# arm_controller_single_v1_1.net
KiCad netlist of a schematic drawn in EAGLE
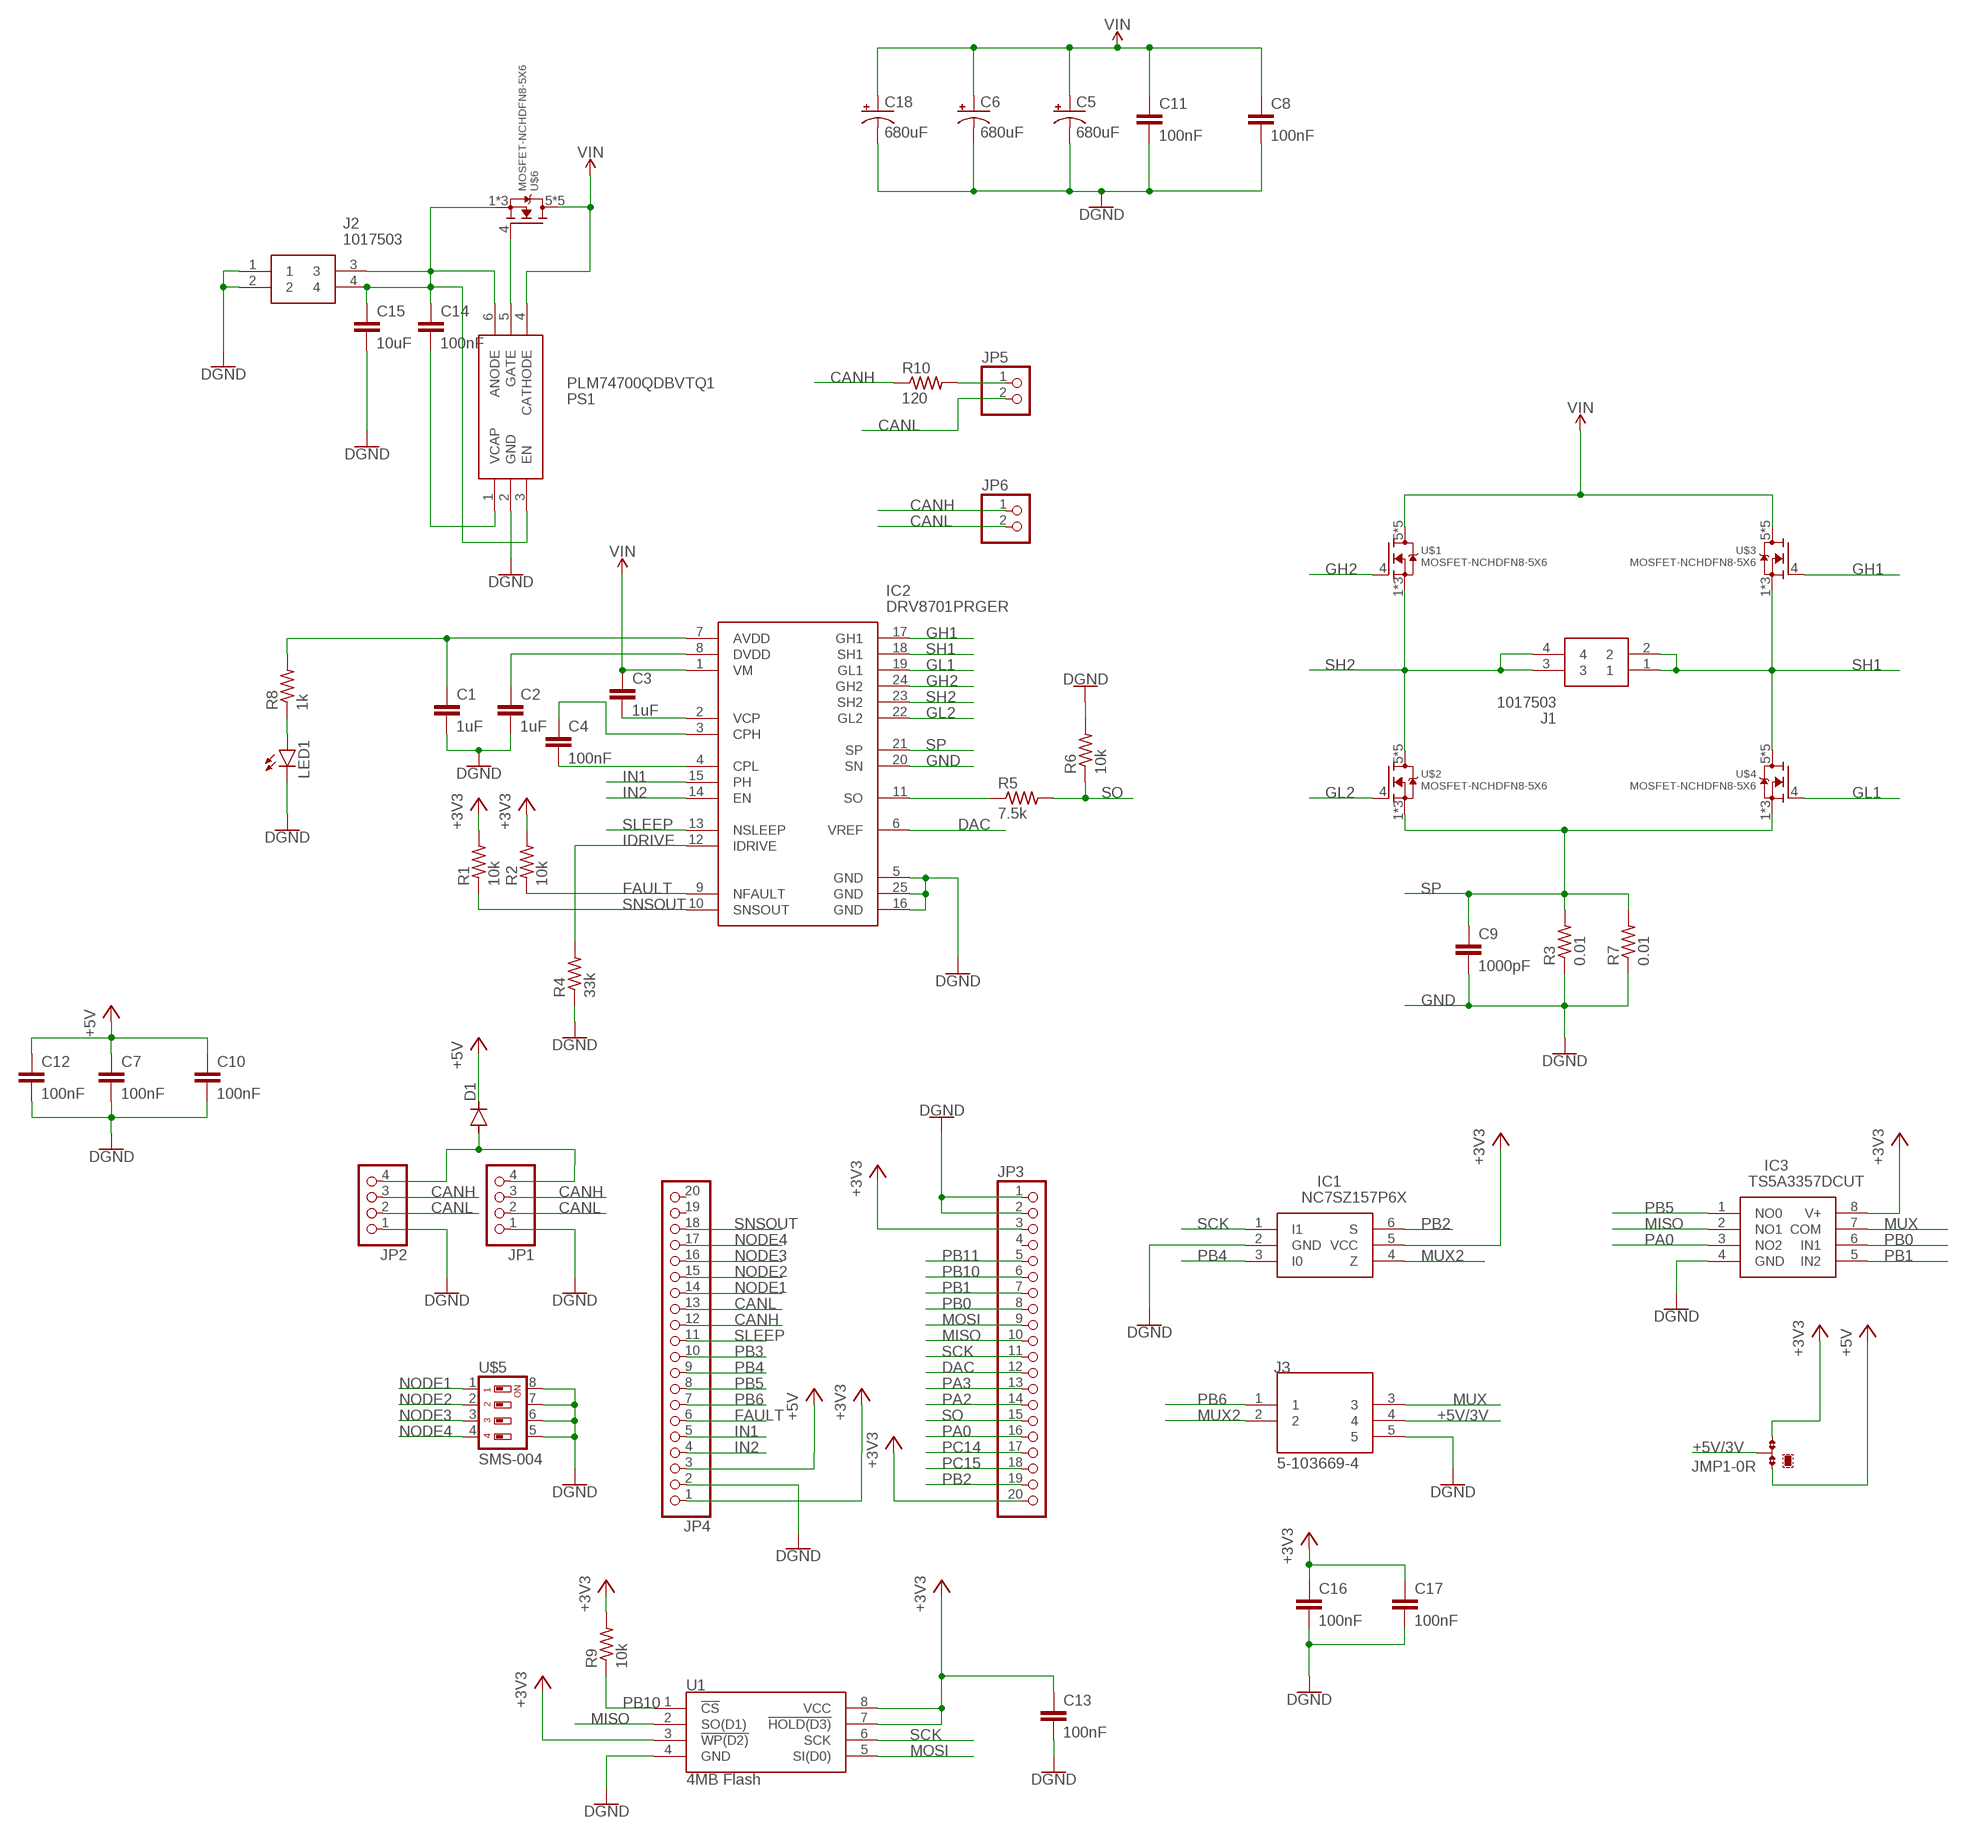
[diagram p0: schematic, sheet 1]

(export (version "E")
  (design (tool "Eeschema 10.0.6"))
  (components
    (comp (ref "C1")
      (value "1uF")
      (footprint "eagle-import:C0603")
      (libsource (lib "eagle-import") (part "C-EUC0603"))
    )
    (comp (ref "C2")
      (value "1uF")
      (footprint "eagle-import:C0603")
      (libsource (lib "eagle-import") (part "C-EUC0603"))
    )
    (comp (ref "C3")
      (value "1uF")
      (footprint "eagle-import:C0603")
      (libsource (lib "eagle-import") (part "C-EUC0603"))
    )
    (comp (ref "C4")
      (value "100nF")
      (footprint "eagle-import:C0603")
      (libsource (lib "eagle-import") (part "C-EUC0603"))
    )
    (comp (ref "C5")
      (value "680uF")
      (footprint "eagle-import:E5-10,5")
      (libsource (lib "eagle-import") (part "CPOL-USE5-10.5"))
    )
    (comp (ref "C6")
      (value "680uF")
      (footprint "eagle-import:E5-10,5")
      (libsource (lib "eagle-import") (part "CPOL-USE5-10.5"))
    )
    (comp (ref "C7")
      (value "100nF")
      (footprint "eagle-import:C0603")
      (libsource (lib "eagle-import") (part "C-EUC0603"))
    )
    (comp (ref "C8")
      (value "100nF")
      (footprint "eagle-import:C0603")
      (libsource (lib "eagle-import") (part "C-EUC0603"))
    )
    (comp (ref "C9")
      (value "1000pF")
      (footprint "eagle-import:C0603")
      (libsource (lib "eagle-import") (part "C-EUC0603"))
    )
    (comp (ref "C10")
      (value "100nF")
      (footprint "eagle-import:C0603")
      (libsource (lib "eagle-import") (part "C-EUC0603"))
    )
    (comp (ref "C11")
      (value "100nF")
      (footprint "eagle-import:C0603")
      (libsource (lib "eagle-import") (part "C-EUC0603"))
    )
    (comp (ref "C12")
      (value "100nF")
      (footprint "eagle-import:C0603")
      (libsource (lib "eagle-import") (part "C-EUC0603"))
    )
    (comp (ref "C13")
      (value "100nF")
      (footprint "eagle-import:C0603")
      (libsource (lib "eagle-import") (part "C-EUC0603"))
    )
    (comp (ref "C14")
      (value "100nF")
      (footprint "eagle-import:C0603")
      (libsource (lib "eagle-import") (part "C-EUC0603"))
    )
    (comp (ref "C15")
      (value "10uF")
      (footprint "eagle-import:C1206")
      (libsource (lib "eagle-import") (part "C-EUC1206"))
    )
    (comp (ref "C16")
      (value "100nF")
      (footprint "eagle-import:C0603")
      (libsource (lib "eagle-import") (part "C-EUC0603"))
    )
    (comp (ref "C17")
      (value "100nF")
      (footprint "eagle-import:C0603")
      (libsource (lib "eagle-import") (part "C-EUC0603"))
    )
    (comp (ref "C18")
      (value "680uF")
      (footprint "eagle-import:E5-10,5")
      (libsource (lib "eagle-import") (part "CPOL-USE5-10.5"))
    )
    (comp (ref "D1")
      (value "CGRM4001-G")
      (footprint "eagle-import:SOD-123_MINI-SMA")
      (libsource (lib "eagle-import") (part "CGRM400-G1"))
    )
    (comp (ref "IC1")
      (value "NC7SZ157P6X")
      (footprint "eagle-import:SOT65P210X110-6N")
      (fields (field (name "MOUSER_PART_NUMBER") "512-NC7SZ157P6X"))
      (libsource (lib "eagle-import") (part "NC7SZ157P6X"))
    )
    (comp (ref "IC2")
      (value "DRV8701PRGER")
      (footprint "eagle-import:QFN50P400X400X100-25N")
      (fields (field (name "MOUSER_PART_NUMBER") "595-DRV8701PRGER"))
      (libsource (lib "eagle-import") (part "DRV8701PRGER"))
    )
    (comp (ref "IC3")
      (value "TS5A3357DCUT")
      (footprint "eagle-import:SOP50P310X90-8N")
      (fields (field (name "MOUSER_PART_NUMBER") "595-TS5A3357DCUT"))
      (libsource (lib "eagle-import") (part "TS5A3357DCUT"))
    )
    (comp (ref "J1")
      (value "1017503")
      (footprint "eagle-import:1017503")
      (fields (field (name "MOUSER_PART_NUMBER") "651-1017503") (field (name "RS_PART_NUMBER") "1753905"))
      (libsource (lib "eagle-import") (part "1017503"))
    )
    (comp (ref "J2")
      (value "1017503")
      (footprint "eagle-import:1017503")
      (fields (field (name "MOUSER_PART_NUMBER") "651-1017503") (field (name "RS_PART_NUMBER") "1753905"))
      (libsource (lib "eagle-import") (part "1017503"))
    )
    (comp (ref "J3")
      (value "5-103669-4")
      (footprint "eagle-import:TE_5-103669-4")
      (fields (field (name "MF") "TE Connectivity"))
      (libsource (lib "eagle-import") (part "5-103669-4"))
    )
    (comp (ref "JMP1")
      (value "0R-JUMPB")
      (footprint "eagle-import:B0R-JMP")
      (libsource (lib "eagle-import") (part "0R-JUMPB"))
    )
    (comp (ref "JP1")
      (value "PINHD-1X4")
      (footprint "eagle-import:1X04")
      (libsource (lib "eagle-import") (part "PINHD-1X4"))
    )
    (comp (ref "JP2")
      (value "PINHD-1X4")
      (footprint "eagle-import:1X04")
      (libsource (lib "eagle-import") (part "PINHD-1X4"))
    )
    (comp (ref "JP3")
      (value "PINHD-1X20")
      (footprint "eagle-import:1X20")
      (libsource (lib "eagle-import") (part "PINHD-1X20"))
    )
    (comp (ref "JP4")
      (value "PINHD-1X20")
      (footprint "eagle-import:1X20")
      (libsource (lib "eagle-import") (part "PINHD-1X20"))
    )
    (comp (ref "JP5")
      (value "PINHD-1X2")
      (footprint "eagle-import:1X02")
      (libsource (lib "eagle-import") (part "PINHD-1X2"))
    )
    (comp (ref "JP6")
      (value "PINHD-1X2")
      (footprint "eagle-import:1X02")
      (libsource (lib "eagle-import") (part "PINHD-1X2"))
    )
    (comp (ref "LED1")
      (value "LEDCHIP-LED0805")
      (footprint "eagle-import:CHIP-LED0805")
      (libsource (lib "eagle-import") (part "LEDCHIP-LED0805"))
    )
    (comp (ref "PS1")
      (value "PLM74700QDBVTQ1")
      (footprint "eagle-import:SOT95P280X145-6N")
      (fields (field (name "MOUSER_PART_NUMBER") "595-PLM74700QDBVTQ1"))
      (libsource (lib "eagle-import") (part "PLM74700QDBVTQ1"))
    )
    (comp (ref "R1")
      (value "10k")
      (footprint "eagle-import:R0603")
      (libsource (lib "eagle-import") (part "R-US_R0603"))
    )
    (comp (ref "R2")
      (value "10k")
      (footprint "eagle-import:R0603")
      (libsource (lib "eagle-import") (part "R-US_R0603"))
    )
    (comp (ref "R3")
      (value "0.01")
      (footprint "eagle-import:R2512")
      (libsource (lib "eagle-import") (part "R-US_R2512"))
    )
    (comp (ref "R4")
      (value "33k")
      (footprint "eagle-import:R0603")
      (libsource (lib "eagle-import") (part "R-US_R0603"))
    )
    (comp (ref "R5")
      (value "7.5k")
      (footprint "eagle-import:R0603")
      (libsource (lib "eagle-import") (part "R-US_R0603"))
    )
    (comp (ref "R6")
      (value "10k")
      (footprint "eagle-import:R0603")
      (libsource (lib "eagle-import") (part "R-US_R0603"))
    )
    (comp (ref "R7")
      (value "0.01")
      (footprint "eagle-import:R2512")
      (libsource (lib "eagle-import") (part "R-US_R2512"))
    )
    (comp (ref "R8")
      (value "1k")
      (footprint "eagle-import:R0603")
      (libsource (lib "eagle-import") (part "R-US_R0603"))
    )
    (comp (ref "R9")
      (value "10k")
      (footprint "eagle-import:R0603")
      (libsource (lib "eagle-import") (part "R-US_R0603"))
    )
    (comp (ref "R10")
      (value "120")
      (footprint "eagle-import:R0603")
      (libsource (lib "eagle-import") (part "R-US_R0603"))
    )
    (comp (ref "U$1")
      (value "MOSFET-NCHDFN8-5X6")
      (footprint "eagle-import:ALOM_DFN5X6_8L_EP1_P")
      (libsource (lib "eagle-import") (part "MOSFET-NCHDFN8-5X6"))
    )
    (comp (ref "U$2")
      (value "MOSFET-NCHDFN8-5X6")
      (footprint "eagle-import:ALOM_DFN5X6_8L_EP1_P")
      (libsource (lib "eagle-import") (part "MOSFET-NCHDFN8-5X6"))
    )
    (comp (ref "U$3")
      (value "MOSFET-NCHDFN8-5X6")
      (footprint "eagle-import:ALOM_DFN5X6_8L_EP1_P")
      (libsource (lib "eagle-import") (part "MOSFET-NCHDFN8-5X6"))
    )
    (comp (ref "U$4")
      (value "MOSFET-NCHDFN8-5X6")
      (footprint "eagle-import:ALOM_DFN5X6_8L_EP1_P")
      (libsource (lib "eagle-import") (part "MOSFET-NCHDFN8-5X6"))
    )
    (comp (ref "U$5")
      (value "SMS-004")
      (footprint "eagle-import:SMS-004")
      (libsource (lib "eagle-import") (part "SMS-004"))
    )
    (comp (ref "U$6")
      (value "MOSFET-NCHDFN8-5X6")
      (footprint "eagle-import:ALOM_DFN5X6_8L_EP1_P")
      (libsource (lib "eagle-import") (part "MOSFET-NCHDFN8-5X6"))
    )
    (comp (ref "U1")
      (value "4MB Flash")
      (footprint "eagle-import:SO08")
      (libsource (lib "eagle-import") (part "AT25SF041"))
    )
  )
  (nets
    (net (code "1") (name "+3V3") (class "Default")
      (node (ref "C13") (pin "1") (pinfunction "1_1") (pintype "passive"))
      (node (ref "C16") (pin "1") (pinfunction "1_1") (pintype "passive"))
      (node (ref "C17") (pin "1") (pinfunction "1_1") (pintype "passive"))
      (node (ref "IC1") (pin "5") (pinfunction "VCC_5") (pintype "power_in"))
      (node (ref "IC3") (pin "8") (pinfunction "V+_8") (pintype "bidirectional"))
      (node (ref "JMP1") (pin "3") (pinfunction "3_3") (pintype "passive"))
      (node (ref "JP3") (pin "20") (pinfunction "20_20") (pintype "passive"))
      (node (ref "JP3") (pin "3") (pinfunction "3_3") (pintype "passive"))
      (node (ref "JP4") (pin "1") (pinfunction "1_1") (pintype "passive"))
      (node (ref "R1") (pin "2") (pinfunction "2_2") (pintype "passive"))
      (node (ref "R2") (pin "2") (pinfunction "2_2") (pintype "passive"))
      (node (ref "R9") (pin "2") (pinfunction "2_2") (pintype "passive"))
      (node (ref "U1") (pin "3") (pinfunction "~{WP(D2})_3") (pintype "bidirectional"))
      (node (ref "U1") (pin "7") (pinfunction "~{HOLD(D3})_7") (pintype "bidirectional"))
      (node (ref "U1") (pin "8") (pinfunction "VCC_8") (pintype "bidirectional"))
    )
    (net (code "2") (name "+5V") (class "Default")
      (node (ref "C10") (pin "1") (pinfunction "1_1") (pintype "passive"))
      (node (ref "C12") (pin "1") (pinfunction "1_1") (pintype "passive"))
      (node (ref "C7") (pin "1") (pinfunction "1_1") (pintype "passive"))
      (node (ref "D1") (pin "C") (pinfunction "C_C") (pintype "passive"))
      (node (ref "JMP1") (pin "1") (pinfunction "1_1") (pintype "passive"))
      (node (ref "JP4") (pin "3") (pinfunction "3_3") (pintype "passive"))
    )
    (net (code "3") (name "/+5V{slash}3V") (class "Default")
      (node (ref "J3") (pin "4") (pinfunction "4_4") (pintype "passive"))
      (node (ref "JMP1") (pin "2") (pinfunction "2_2") (pintype "passive"))
    )
    (net (code "4") (name "/CANH") (class "Default")
      (node (ref "JP1") (pin "3") (pinfunction "3_3") (pintype "passive"))
      (node (ref "JP2") (pin "3") (pinfunction "3_3") (pintype "passive"))
      (node (ref "JP4") (pin "12") (pinfunction "12_12") (pintype "passive"))
      (node (ref "JP6") (pin "1") (pinfunction "1_1") (pintype "passive"))
      (node (ref "R10") (pin "1") (pinfunction "1_1") (pintype "passive"))
    )
    (net (code "5") (name "/CANL") (class "Default")
      (node (ref "JP1") (pin "2") (pinfunction "2_2") (pintype "passive"))
      (node (ref "JP2") (pin "2") (pinfunction "2_2") (pintype "passive"))
      (node (ref "JP4") (pin "13") (pinfunction "13_13") (pintype "passive"))
      (node (ref "JP5") (pin "2") (pinfunction "2_2") (pintype "passive"))
      (node (ref "JP6") (pin "2") (pinfunction "2_2") (pintype "passive"))
    )
    (net (code "6") (name "/DAC") (class "Default")
      (node (ref "IC2") (pin "6") (pinfunction "VREF_6") (pintype "bidirectional"))
      (node (ref "JP3") (pin "12") (pinfunction "12_12") (pintype "passive"))
    )
    (net (code "7") (name "/FAULT") (class "Default")
      (node (ref "IC2") (pin "9") (pinfunction "NFAULT_9") (pintype "bidirectional"))
      (node (ref "JP4") (pin "6") (pinfunction "6_6") (pintype "passive"))
      (node (ref "R2") (pin "1") (pinfunction "1_1") (pintype "passive"))
    )
    (net (code "8") (name "/GH1") (class "Default")
      (node (ref "IC2") (pin "17") (pinfunction "GH1_17") (pintype "bidirectional"))
      (node (ref "U$3") (pin "4") (pinfunction "G_4") (pintype "bidirectional"))
    )
    (net (code "9") (name "/GH2") (class "Default")
      (node (ref "IC2") (pin "24") (pinfunction "GH2_24") (pintype "bidirectional"))
      (node (ref "U$1") (pin "4") (pinfunction "G_4") (pintype "bidirectional"))
    )
    (net (code "10") (name "/GL1") (class "Default")
      (node (ref "IC2") (pin "19") (pinfunction "GL1_19") (pintype "bidirectional"))
      (node (ref "U$4") (pin "4") (pinfunction "G_4") (pintype "bidirectional"))
    )
    (net (code "11") (name "/GL2") (class "Default")
      (node (ref "IC2") (pin "22") (pinfunction "GL2_22") (pintype "bidirectional"))
      (node (ref "U$2") (pin "4") (pinfunction "G_4") (pintype "bidirectional"))
    )
    (net (code "12") (name "/IDRIVE") (class "Default")
      (node (ref "IC2") (pin "12") (pinfunction "IDRIVE_12") (pintype "bidirectional"))
      (node (ref "R4") (pin "2") (pinfunction "2_2") (pintype "passive"))
    )
    (net (code "13") (name "/IN1") (class "Default")
      (node (ref "IC2") (pin "15") (pinfunction "PH_15") (pintype "bidirectional"))
      (node (ref "JP4") (pin "5") (pinfunction "5_5") (pintype "passive"))
    )
    (net (code "14") (name "/IN2") (class "Default")
      (node (ref "IC2") (pin "14") (pinfunction "EN_14") (pintype "bidirectional"))
      (node (ref "JP4") (pin "4") (pinfunction "4_4") (pintype "passive"))
    )
    (net (code "15") (name "/MISO") (class "Default")
      (node (ref "IC3") (pin "2") (pinfunction "NO1_2") (pintype "bidirectional"))
      (node (ref "JP3") (pin "10") (pinfunction "10_10") (pintype "passive"))
      (node (ref "U1") (pin "2") (pinfunction "SO(D1)_2") (pintype "bidirectional"))
    )
    (net (code "16") (name "/MOSI") (class "Default")
      (node (ref "JP3") (pin "9") (pinfunction "9_9") (pintype "passive"))
      (node (ref "U1") (pin "5") (pinfunction "SI(D0)_5") (pintype "bidirectional"))
    )
    (net (code "17") (name "/MUX") (class "Default")
      (node (ref "IC3") (pin "7") (pinfunction "COM_7") (pintype "bidirectional"))
      (node (ref "J3") (pin "3") (pinfunction "3_3") (pintype "passive"))
    )
    (net (code "18") (name "/MUX2") (class "Default")
      (node (ref "IC1") (pin "4") (pinfunction "Z_4") (pintype "output"))
      (node (ref "J3") (pin "2") (pinfunction "2_2") (pintype "passive"))
    )
    (net (code "19") (name "/NODE1") (class "Default")
      (node (ref "JP4") (pin "14") (pinfunction "14_14") (pintype "passive"))
      (node (ref "U$5") (pin "1") (pinfunction "1_1") (pintype "passive"))
    )
    (net (code "20") (name "/NODE2") (class "Default")
      (node (ref "JP4") (pin "15") (pinfunction "15_15") (pintype "passive"))
      (node (ref "U$5") (pin "2") (pinfunction "2_2") (pintype "passive"))
    )
    (net (code "21") (name "/NODE3") (class "Default")
      (node (ref "JP4") (pin "16") (pinfunction "16_16") (pintype "passive"))
      (node (ref "U$5") (pin "3") (pinfunction "3_3") (pintype "passive"))
    )
    (net (code "22") (name "/NODE4") (class "Default")
      (node (ref "JP4") (pin "17") (pinfunction "17_17") (pintype "passive"))
      (node (ref "U$5") (pin "4") (pinfunction "4_4") (pintype "passive"))
    )
    (net (code "23") (name "/PA0") (class "Default")
      (node (ref "IC3") (pin "3") (pinfunction "NO2_3") (pintype "bidirectional"))
      (node (ref "JP3") (pin "16") (pinfunction "16_16") (pintype "passive"))
    )
    (net (code "24") (name "/PA2") (class "Default")
      (node (ref "JP3") (pin "14") (pinfunction "14_14") (pintype "passive"))
    )
    (net (code "25") (name "/PA3") (class "Default")
      (node (ref "JP3") (pin "13") (pinfunction "13_13") (pintype "passive"))
    )
    (net (code "26") (name "/PB0") (class "Default")
      (node (ref "IC3") (pin "6") (pinfunction "IN1_6") (pintype "input"))
      (node (ref "JP3") (pin "8") (pinfunction "8_8") (pintype "passive"))
    )
    (net (code "27") (name "/PB1") (class "Default")
      (node (ref "IC3") (pin "5") (pinfunction "IN2_5") (pintype "input"))
      (node (ref "JP3") (pin "7") (pinfunction "7_7") (pintype "passive"))
    )
    (net (code "28") (name "/PB2") (class "Default")
      (node (ref "IC1") (pin "6") (pinfunction "S_6") (pintype "input"))
      (node (ref "JP3") (pin "19") (pinfunction "19_19") (pintype "passive"))
    )
    (net (code "29") (name "/PB3") (class "Default")
      (node (ref "JP4") (pin "10") (pinfunction "10_10") (pintype "passive"))
    )
    (net (code "30") (name "/PB4") (class "Default")
      (node (ref "IC1") (pin "3") (pinfunction "I0_3") (pintype "input"))
      (node (ref "JP4") (pin "9") (pinfunction "9_9") (pintype "passive"))
    )
    (net (code "31") (name "/PB5") (class "Default")
      (node (ref "IC3") (pin "1") (pinfunction "NO0_1") (pintype "bidirectional"))
      (node (ref "JP4") (pin "8") (pinfunction "8_8") (pintype "passive"))
    )
    (net (code "32") (name "/PB6") (class "Default")
      (node (ref "J3") (pin "1") (pinfunction "1_1") (pintype "passive"))
      (node (ref "JP4") (pin "7") (pinfunction "7_7") (pintype "passive"))
    )
    (net (code "33") (name "/PB10") (class "Default")
      (node (ref "JP3") (pin "6") (pinfunction "6_6") (pintype "passive"))
      (node (ref "R9") (pin "1") (pinfunction "1_1") (pintype "passive"))
      (node (ref "U1") (pin "1") (pinfunction "~{CS}_1") (pintype "bidirectional"))
    )
    (net (code "34") (name "/PB11") (class "Default")
      (node (ref "JP3") (pin "5") (pinfunction "5_5") (pintype "passive"))
    )
    (net (code "35") (name "/PC14") (class "Default")
      (node (ref "JP3") (pin "17") (pinfunction "17_17") (pintype "passive"))
    )
    (net (code "36") (name "/PC15") (class "Default")
      (node (ref "JP3") (pin "18") (pinfunction "18_18") (pintype "passive"))
    )
    (net (code "37") (name "/SCK") (class "Default")
      (node (ref "IC1") (pin "1") (pinfunction "I1_1") (pintype "input"))
      (node (ref "JP3") (pin "11") (pinfunction "11_11") (pintype "passive"))
      (node (ref "U1") (pin "6") (pinfunction "SCK_6") (pintype "bidirectional"))
    )
    (net (code "38") (name "/SH1") (class "Default")
      (node (ref "IC2") (pin "18") (pinfunction "SH1_18") (pintype "bidirectional"))
      (node (ref "J1") (pin "1") (pinfunction "1_1") (pintype "bidirectional"))
      (node (ref "J1") (pin "2") (pinfunction "2_2") (pintype "bidirectional"))
      (node (ref "U$3") (pin "1") (pinfunction "S_1") (pintype "bidirectional"))
      (node (ref "U$3") (pin "2") (pinfunction "S_2") (pintype "bidirectional"))
      (node (ref "U$3") (pin "3") (pinfunction "S_3") (pintype "bidirectional"))
      (node (ref "U$4") (pin "5") (pinfunction "D_5") (pintype "bidirectional"))
      (node (ref "U$4") (pin "6") (pinfunction "D_6") (pintype "bidirectional"))
      (node (ref "U$4") (pin "7") (pinfunction "D_7") (pintype "bidirectional"))
      (node (ref "U$4") (pin "8") (pinfunction "D_8") (pintype "bidirectional"))
      (node (ref "U$4") (pin "9") (pinfunction "D_9") (pintype "bidirectional"))
    )
    (net (code "39") (name "/SH2") (class "Default")
      (node (ref "IC2") (pin "23") (pinfunction "SH2_23") (pintype "bidirectional"))
      (node (ref "J1") (pin "3") (pinfunction "3_3") (pintype "bidirectional"))
      (node (ref "J1") (pin "4") (pinfunction "4_4") (pintype "bidirectional"))
      (node (ref "U$1") (pin "1") (pinfunction "S_1") (pintype "bidirectional"))
      (node (ref "U$1") (pin "2") (pinfunction "S_2") (pintype "bidirectional"))
      (node (ref "U$1") (pin "3") (pinfunction "S_3") (pintype "bidirectional"))
      (node (ref "U$2") (pin "5") (pinfunction "D_5") (pintype "bidirectional"))
      (node (ref "U$2") (pin "6") (pinfunction "D_6") (pintype "bidirectional"))
      (node (ref "U$2") (pin "7") (pinfunction "D_7") (pintype "bidirectional"))
      (node (ref "U$2") (pin "8") (pinfunction "D_8") (pintype "bidirectional"))
      (node (ref "U$2") (pin "9") (pinfunction "D_9") (pintype "bidirectional"))
    )
    (net (code "40") (name "/SLEEP") (class "Default")
      (node (ref "IC2") (pin "13") (pinfunction "NSLEEP_13") (pintype "bidirectional"))
      (node (ref "JP4") (pin "11") (pinfunction "11_11") (pintype "passive"))
    )
    (net (code "41") (name "/SNSOUT") (class "Default")
      (node (ref "IC2") (pin "10") (pinfunction "SNSOUT_10") (pintype "bidirectional"))
      (node (ref "JP4") (pin "18") (pinfunction "18_18") (pintype "passive"))
      (node (ref "R1") (pin "1") (pinfunction "1_1") (pintype "passive"))
    )
    (net (code "42") (name "/SO") (class "Default")
      (node (ref "JP3") (pin "15") (pinfunction "15_15") (pintype "passive"))
      (node (ref "R5") (pin "2") (pinfunction "2_2") (pintype "passive"))
      (node (ref "R6") (pin "1") (pinfunction "1_1") (pintype "passive"))
    )
    (net (code "43") (name "/SP") (class "Default")
      (node (ref "C9") (pin "1") (pinfunction "1_1") (pintype "passive"))
      (node (ref "IC2") (pin "21") (pinfunction "SP_21") (pintype "bidirectional"))
      (node (ref "R3") (pin "2") (pinfunction "2_2") (pintype "passive"))
      (node (ref "R7") (pin "2") (pinfunction "2_2") (pintype "passive"))
      (node (ref "U$2") (pin "1") (pinfunction "S_1") (pintype "bidirectional"))
      (node (ref "U$2") (pin "2") (pinfunction "S_2") (pintype "bidirectional"))
      (node (ref "U$2") (pin "3") (pinfunction "S_3") (pintype "bidirectional"))
      (node (ref "U$4") (pin "1") (pinfunction "S_1") (pintype "bidirectional"))
      (node (ref "U$4") (pin "2") (pinfunction "S_2") (pintype "bidirectional"))
      (node (ref "U$4") (pin "3") (pinfunction "S_3") (pintype "bidirectional"))
    )
    (net (code "44") (name "DGND") (class "Default")
      (node (ref "C1") (pin "2") (pinfunction "2_2") (pintype "passive"))
      (node (ref "C10") (pin "2") (pinfunction "2_2") (pintype "passive"))
      (node (ref "C11") (pin "2") (pinfunction "2_2") (pintype "passive"))
      (node (ref "C12") (pin "2") (pinfunction "2_2") (pintype "passive"))
      (node (ref "C13") (pin "2") (pinfunction "2_2") (pintype "passive"))
      (node (ref "C15") (pin "2") (pinfunction "2_2") (pintype "passive"))
      (node (ref "C16") (pin "2") (pinfunction "2_2") (pintype "passive"))
      (node (ref "C17") (pin "2") (pinfunction "2_2") (pintype "passive"))
      (node (ref "C18") (pin "-") (pinfunction "-_-") (pintype "passive"))
      (node (ref "C2") (pin "2") (pinfunction "2_2") (pintype "passive"))
      (node (ref "C5") (pin "-") (pinfunction "-_-") (pintype "passive"))
      (node (ref "C6") (pin "-") (pinfunction "-_-") (pintype "passive"))
      (node (ref "C7") (pin "2") (pinfunction "2_2") (pintype "passive"))
      (node (ref "C8") (pin "2") (pinfunction "2_2") (pintype "passive"))
      (node (ref "C9") (pin "2") (pinfunction "2_2") (pintype "passive"))
      (node (ref "IC1") (pin "2") (pinfunction "GND_2") (pintype "power_in"))
      (node (ref "IC2") (pin "16") (pinfunction "GND_16") (pintype "bidirectional"))
      (node (ref "IC2") (pin "20") (pinfunction "SN_20") (pintype "bidirectional"))
      (node (ref "IC2") (pin "25") (pinfunction "GND_25") (pintype "bidirectional"))
      (node (ref "IC2") (pin "5") (pinfunction "GND_5") (pintype "bidirectional"))
      (node (ref "IC3") (pin "4") (pinfunction "GND_4") (pintype "power_in"))
      (node (ref "J2") (pin "1") (pinfunction "1_1") (pintype "bidirectional"))
      (node (ref "J2") (pin "2") (pinfunction "2_2") (pintype "bidirectional"))
      (node (ref "J3") (pin "5") (pinfunction "5_5") (pintype "passive"))
      (node (ref "JP1") (pin "1") (pinfunction "1_1") (pintype "passive"))
      (node (ref "JP2") (pin "1") (pinfunction "1_1") (pintype "passive"))
      (node (ref "JP3") (pin "1") (pinfunction "1_1") (pintype "passive"))
      (node (ref "JP3") (pin "2") (pinfunction "2_2") (pintype "passive"))
      (node (ref "JP4") (pin "2") (pinfunction "2_2") (pintype "passive"))
      (node (ref "LED1") (pin "C") (pinfunction "C_C") (pintype "passive"))
      (node (ref "PS1") (pin "2") (pinfunction "GND_2") (pintype "power_in"))
      (node (ref "R3") (pin "1") (pinfunction "1_1") (pintype "passive"))
      (node (ref "R4") (pin "1") (pinfunction "1_1") (pintype "passive"))
      (node (ref "R6") (pin "2") (pinfunction "2_2") (pintype "passive"))
      (node (ref "R7") (pin "1") (pinfunction "1_1") (pintype "passive"))
      (node (ref "U$5") (pin "5") (pinfunction "5_5") (pintype "passive"))
      (node (ref "U$5") (pin "6") (pinfunction "6_6") (pintype "passive"))
      (node (ref "U$5") (pin "7") (pinfunction "7_7") (pintype "passive"))
      (node (ref "U$5") (pin "8") (pinfunction "8_8") (pintype "passive"))
      (node (ref "U1") (pin "4") (pinfunction "GND_4") (pintype "bidirectional"))
    )
    (net (code "45") (name "Net-(D1-PadA)") (class "Default")
      (node (ref "D1") (pin "A") (pinfunction "A_A") (pintype "passive"))
      (node (ref "JP1") (pin "4") (pinfunction "4_4") (pintype "passive"))
      (node (ref "JP2") (pin "4") (pinfunction "4_4") (pintype "passive"))
    )
    (net (code "46") (name "Net-(IC2-AVDD)") (class "Default")
      (node (ref "C1") (pin "1") (pinfunction "1_1") (pintype "passive"))
      (node (ref "IC2") (pin "7") (pinfunction "AVDD_7") (pintype "bidirectional"))
      (node (ref "R8") (pin "2") (pinfunction "2_2") (pintype "passive"))
    )
    (net (code "47") (name "Net-(IC2-CPH)") (class "Default")
      (node (ref "C4") (pin "1") (pinfunction "1_1") (pintype "passive"))
      (node (ref "IC2") (pin "3") (pinfunction "CPH_3") (pintype "bidirectional"))
    )
    (net (code "48") (name "Net-(IC2-CPL)") (class "Default")
      (node (ref "C4") (pin "2") (pinfunction "2_2") (pintype "passive"))
      (node (ref "IC2") (pin "4") (pinfunction "CPL_4") (pintype "bidirectional"))
    )
    (net (code "49") (name "Net-(IC2-DVDD)") (class "Default")
      (node (ref "C2") (pin "1") (pinfunction "1_1") (pintype "passive"))
      (node (ref "IC2") (pin "8") (pinfunction "DVDD_8") (pintype "bidirectional"))
    )
    (net (code "50") (name "Net-(IC2-SO)") (class "Default")
      (node (ref "IC2") (pin "11") (pinfunction "SO_11") (pintype "bidirectional"))
      (node (ref "R5") (pin "1") (pinfunction "1_1") (pintype "passive"))
    )
    (net (code "51") (name "Net-(IC2-VCP)") (class "Default")
      (node (ref "C3") (pin "2") (pinfunction "2_2") (pintype "passive"))
      (node (ref "IC2") (pin "2") (pinfunction "VCP_2") (pintype "bidirectional"))
    )
    (net (code "52") (name "Net-(JP5-Pad1)") (class "Default")
      (node (ref "JP5") (pin "1") (pinfunction "1_1") (pintype "passive"))
      (node (ref "R10") (pin "2") (pinfunction "2_2") (pintype "passive"))
    )
    (net (code "53") (name "Net-(LED1-PadA)") (class "Default")
      (node (ref "LED1") (pin "A") (pinfunction "A_A") (pintype "passive"))
      (node (ref "R8") (pin "1") (pinfunction "1_1") (pintype "passive"))
    )
    (net (code "54") (name "Net-(PS1-ANODE)") (class "Default")
      (node (ref "C14") (pin "1") (pinfunction "1_1") (pintype "passive"))
      (node (ref "C15") (pin "1") (pinfunction "1_1") (pintype "passive"))
      (node (ref "J2") (pin "3") (pinfunction "3_3") (pintype "bidirectional"))
      (node (ref "J2") (pin "4") (pinfunction "4_4") (pintype "bidirectional"))
      (node (ref "PS1") (pin "3") (pinfunction "EN_3") (pintype "input"))
      (node (ref "PS1") (pin "6") (pinfunction "ANODE_6") (pintype "bidirectional"))
      (node (ref "U$6") (pin "1") (pinfunction "S_1") (pintype "bidirectional"))
      (node (ref "U$6") (pin "2") (pinfunction "S_2") (pintype "bidirectional"))
      (node (ref "U$6") (pin "3") (pinfunction "S_3") (pintype "bidirectional"))
    )
    (net (code "55") (name "Net-(PS1-GATE)") (class "Default")
      (node (ref "PS1") (pin "5") (pinfunction "GATE_5") (pintype "output"))
      (node (ref "U$6") (pin "4") (pinfunction "G_4") (pintype "bidirectional"))
    )
    (net (code "56") (name "Net-(PS1-VCAP)") (class "Default")
      (node (ref "C14") (pin "2") (pinfunction "2_2") (pintype "passive"))
      (node (ref "PS1") (pin "1") (pinfunction "VCAP_1") (pintype "bidirectional"))
    )
    (net (code "57") (name "VIN") (class "Default")
      (node (ref "C11") (pin "1") (pinfunction "1_1") (pintype "passive"))
      (node (ref "C18") (pin "+") (pinfunction "+_+") (pintype "passive"))
      (node (ref "C3") (pin "1") (pinfunction "1_1") (pintype "passive"))
      (node (ref "C5") (pin "+") (pinfunction "+_+") (pintype "passive"))
      (node (ref "C6") (pin "+") (pinfunction "+_+") (pintype "passive"))
      (node (ref "C8") (pin "1") (pinfunction "1_1") (pintype "passive"))
      (node (ref "IC2") (pin "1") (pinfunction "VM_1") (pintype "bidirectional"))
      (node (ref "PS1") (pin "4") (pinfunction "CATHODE_4") (pintype "bidirectional"))
      (node (ref "U$1") (pin "5") (pinfunction "D_5") (pintype "bidirectional"))
      (node (ref "U$1") (pin "6") (pinfunction "D_6") (pintype "bidirectional"))
      (node (ref "U$1") (pin "7") (pinfunction "D_7") (pintype "bidirectional"))
      (node (ref "U$1") (pin "8") (pinfunction "D_8") (pintype "bidirectional"))
      (node (ref "U$1") (pin "9") (pinfunction "D_9") (pintype "bidirectional"))
      (node (ref "U$3") (pin "5") (pinfunction "D_5") (pintype "bidirectional"))
      (node (ref "U$3") (pin "6") (pinfunction "D_6") (pintype "bidirectional"))
      (node (ref "U$3") (pin "7") (pinfunction "D_7") (pintype "bidirectional"))
      (node (ref "U$3") (pin "8") (pinfunction "D_8") (pintype "bidirectional"))
      (node (ref "U$3") (pin "9") (pinfunction "D_9") (pintype "bidirectional"))
      (node (ref "U$6") (pin "5") (pinfunction "D_5") (pintype "bidirectional"))
      (node (ref "U$6") (pin "6") (pinfunction "D_6") (pintype "bidirectional"))
      (node (ref "U$6") (pin "7") (pinfunction "D_7") (pintype "bidirectional"))
      (node (ref "U$6") (pin "8") (pinfunction "D_8") (pintype "bidirectional"))
      (node (ref "U$6") (pin "9") (pinfunction "D_9") (pintype "bidirectional"))
    )
    (net (code "58") (name "unconnected-(JP3-Pad4)") (class "Default")
      (node (ref "JP3") (pin "4") (pinfunction "4_4") (pintype "passive"))
    )
    (net (code "59") (name "unconnected-(JP4-Pad19)") (class "Default")
      (node (ref "JP4") (pin "19") (pinfunction "19_19") (pintype "passive"))
    )
    (net (code "60") (name "unconnected-(JP4-Pad20)") (class "Default")
      (node (ref "JP4") (pin "20") (pinfunction "20_20") (pintype "passive"))
    )
  )
)
